# purza.net
KiCad netlist of a schematic drawn in EAGLE
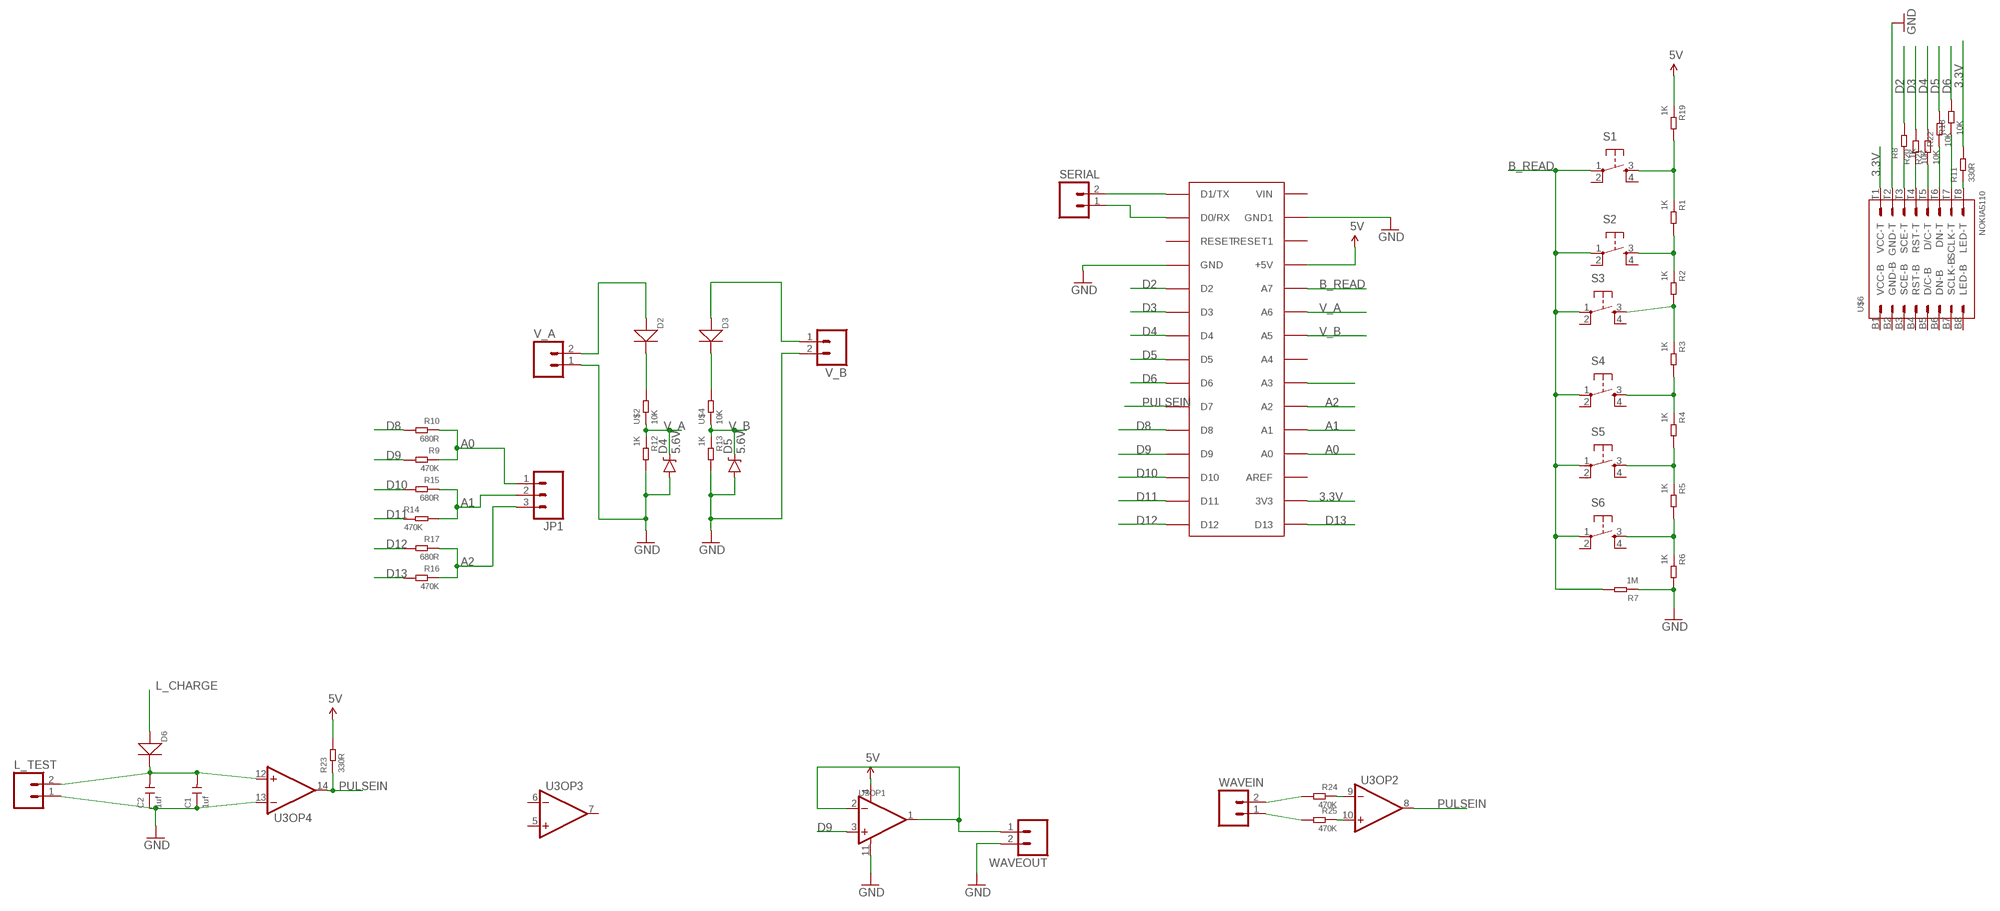
[diagram p0: schematic, sheet 1]

(export (version "E")
  (design (tool "Eeschema 10.0.6"))
  (components
    (comp (ref "C1")
      (value "1uf")
      (footprint "eagle-import:C0805")
      (fields (field (name "MPN") "CC0805KKX7R8BB105"))
      (libsource (lib "eagle-import") (part "CERAMIC-1UF-25V-10%-X7R(0805)"))
    )
    (comp (ref "C2")
      (value "1uf")
      (footprint "eagle-import:C0805")
      (fields (field (name "MPN") "CC0805KKX7R8BB105"))
      (libsource (lib "eagle-import") (part "CERAMIC-1UF-25V-10%-X7R(0805)"))
    )
    (comp (ref "D2")
      (value "DIODE'1206'")
      (footprint "eagle-import:SOD-123")
      (libsource (lib "eagle-import") (part "DIODE'1206'"))
    )
    (comp (ref "D3")
      (value "DIODE'1206'")
      (footprint "eagle-import:SOD-123")
      (libsource (lib "eagle-import") (part "DIODE'1206'"))
    )
    (comp (ref "D4")
      (value "5.6V")
      (footprint "eagle-import:SOD-323")
      (libsource (lib "eagle-import") (part "DIODE-ZENER5.6V"))
    )
    (comp (ref "D5")
      (value "5.6V")
      (footprint "eagle-import:SOD-323")
      (libsource (lib "eagle-import") (part "DIODE-ZENER5.6V"))
    )
    (comp (ref "D6")
      (value "DIODE'1206'")
      (footprint "eagle-import:SOD-123")
      (libsource (lib "eagle-import") (part "DIODE'1206'"))
    )
    (comp (ref "JP1")
      (value "M03LOCK")
      (footprint "eagle-import:1X03_LOCK")
      (libsource (lib "eagle-import") (part "M03LOCK"))
    )
    (comp (ref "L_TEST")
      (value "M02LOCK")
      (footprint "eagle-import:1X02_LOCK")
      (libsource (lib "eagle-import") (part "M02LOCK"))
    )
    (comp (ref "R1")
      (value "1K")
      (footprint "eagle-import:R0603")
      (fields (field (name "MPN") "RC0603FR-071KL"))
      (libsource (lib "eagle-import") (part "SMD-RES-1K-1%-1/10W(0603)"))
    )
    (comp (ref "R2")
      (value "1K")
      (footprint "eagle-import:R0603")
      (fields (field (name "MPN") "RC0603FR-071KL"))
      (libsource (lib "eagle-import") (part "SMD-RES-1K-1%-1/10W(0603)"))
    )
    (comp (ref "R3")
      (value "1K")
      (footprint "eagle-import:R0603")
      (fields (field (name "MPN") "RC0603FR-071KL"))
      (libsource (lib "eagle-import") (part "SMD-RES-1K-1%-1/10W(0603)"))
    )
    (comp (ref "R4")
      (value "1K")
      (footprint "eagle-import:R0603")
      (fields (field (name "MPN") "RC0603FR-071KL"))
      (libsource (lib "eagle-import") (part "SMD-RES-1K-1%-1/10W(0603)"))
    )
    (comp (ref "R5")
      (value "1K")
      (footprint "eagle-import:R0603")
      (fields (field (name "MPN") "RC0603FR-071KL"))
      (libsource (lib "eagle-import") (part "SMD-RES-1K-1%-1/10W(0603)"))
    )
    (comp (ref "R6")
      (value "1K")
      (footprint "eagle-import:R0603")
      (fields (field (name "MPN") "RC0603FR-071KL"))
      (libsource (lib "eagle-import") (part "SMD-RES-1K-1%-1/10W(0603)"))
    )
    (comp (ref "R7")
      (value "1M")
      (footprint "eagle-import:R0603")
      (fields (field (name "MPN") "RC0603FR-071ML"))
      (libsource (lib "eagle-import") (part "SMD-RES-1M-1%-1/10W(0603)"))
    )
    (comp (ref "R8")
      (value "1K")
      (footprint "eagle-import:R0603")
      (fields (field (name "MPN") "RC0603FR-071KL"))
      (libsource (lib "eagle-import") (part "SMD-RES-1K-1%-1/10W(0603)"))
    )
    (comp (ref "R9")
      (value "470K")
      (footprint "eagle-import:R0603")
      (fields (field (name "MPN") "RC0603FR-07470KL"))
      (libsource (lib "eagle-import") (part "SMD-RES-470K-1%-1/10W(0603)"))
    )
    (comp (ref "R10")
      (value "680R")
      (footprint "eagle-import:R0603")
      (fields (field (name "MPN") "RC0603FR-07680RL"))
      (libsource (lib "eagle-import") (part "SMD-RES-680R-1%-1/10W(0603)"))
    )
    (comp (ref "R11")
      (value "330R")
      (footprint "eagle-import:R0603")
      (fields (field (name "MPN") "RC0603FR-07330RL"))
      (libsource (lib "eagle-import") (part "SMD-RES-330R-1%-1/10W(0603)"))
    )
    (comp (ref "R12")
      (value "1K")
      (footprint "eagle-import:R0603")
      (fields (field (name "MPN") "RC0603FR-071KL"))
      (libsource (lib "eagle-import") (part "SMD-RES-1K-1%-1/10W(0603)"))
    )
    (comp (ref "R13")
      (value "1K")
      (footprint "eagle-import:R0603")
      (fields (field (name "MPN") "RC0603FR-071KL"))
      (libsource (lib "eagle-import") (part "SMD-RES-1K-1%-1/10W(0603)"))
    )
    (comp (ref "R14")
      (value "470K")
      (footprint "eagle-import:R0603")
      (fields (field (name "MPN") "RC0603FR-07470KL"))
      (libsource (lib "eagle-import") (part "SMD-RES-470K-1%-1/10W(0603)"))
    )
    (comp (ref "R15")
      (value "680R")
      (footprint "eagle-import:R0603")
      (fields (field (name "MPN") "RC0603FR-07680RL"))
      (libsource (lib "eagle-import") (part "SMD-RES-680R-1%-1/10W(0603)"))
    )
    (comp (ref "R16")
      (value "470K")
      (footprint "eagle-import:R0603")
      (fields (field (name "MPN") "RC0603FR-07470KL"))
      (libsource (lib "eagle-import") (part "SMD-RES-470K-1%-1/10W(0603)"))
    )
    (comp (ref "R17")
      (value "680R")
      (footprint "eagle-import:R0603")
      (fields (field (name "MPN") "RC0603FR-07680RL"))
      (libsource (lib "eagle-import") (part "SMD-RES-680R-1%-1/10W(0603)"))
    )
    (comp (ref "R18")
      (value "10K")
      (footprint "eagle-import:R0603")
      (fields (field (name "MPN") "RC0603FR-0710KL"))
      (libsource (lib "eagle-import") (part "SMD-RES-10K-1%-1/10W(0603)"))
    )
    (comp (ref "R19")
      (value "1K")
      (footprint "eagle-import:R0603")
      (fields (field (name "MPN") "RC0603FR-071KL"))
      (libsource (lib "eagle-import") (part "SMD-RES-1K-1%-1/10W(0603)"))
    )
    (comp (ref "R20")
      (value "10K")
      (footprint "eagle-import:R0603")
      (fields (field (name "MPN") "RC0603FR-0710KL"))
      (libsource (lib "eagle-import") (part "SMD-RES-10K-1%-1/10W(0603)"))
    )
    (comp (ref "R21")
      (value "10K")
      (footprint "eagle-import:R0603")
      (fields (field (name "MPN") "RC0603FR-0710KL"))
      (libsource (lib "eagle-import") (part "SMD-RES-10K-1%-1/10W(0603)"))
    )
    (comp (ref "R22")
      (value "10K")
      (footprint "eagle-import:R0603")
      (fields (field (name "MPN") "RC0603FR-0710KL"))
      (libsource (lib "eagle-import") (part "SMD-RES-10K-1%-1/10W(0603)"))
    )
    (comp (ref "R23")
      (value "330R")
      (footprint "eagle-import:R0603")
      (fields (field (name "MPN") "RC0603FR-07330RL"))
      (libsource (lib "eagle-import") (part "SMD-RES-330R-1%-1/10W(0603)"))
    )
    (comp (ref "R24")
      (value "470K")
      (footprint "eagle-import:R0603")
      (fields (field (name "MPN") "RC0603FR-07470KL"))
      (libsource (lib "eagle-import") (part "SMD-RES-470K-1%-1/10W(0603)"))
    )
    (comp (ref "R25")
      (value "470K")
      (footprint "eagle-import:R0603")
      (fields (field (name "MPN") "RC0603FR-07470KL"))
      (libsource (lib "eagle-import") (part "SMD-RES-470K-1%-1/10W(0603)"))
    )
    (comp (ref "S1")
      (value "TAC_SWITCHPTH")
      (footprint "eagle-import:TACTILE-PTH")
      (libsource (lib "eagle-import") (part "TAC_SWITCHPTH"))
    )
    (comp (ref "S2")
      (value "TAC_SWITCHPTH")
      (footprint "eagle-import:TACTILE-PTH")
      (libsource (lib "eagle-import") (part "TAC_SWITCHPTH"))
    )
    (comp (ref "S3")
      (value "TAC_SWITCHPTH")
      (footprint "eagle-import:TACTILE-PTH")
      (libsource (lib "eagle-import") (part "TAC_SWITCHPTH"))
    )
    (comp (ref "S4")
      (value "TAC_SWITCHPTH")
      (footprint "eagle-import:TACTILE-PTH")
      (libsource (lib "eagle-import") (part "TAC_SWITCHPTH"))
    )
    (comp (ref "S5")
      (value "TAC_SWITCHPTH")
      (footprint "eagle-import:TACTILE-PTH")
      (libsource (lib "eagle-import") (part "TAC_SWITCHPTH"))
    )
    (comp (ref "S6")
      (value "TAC_SWITCHPTH")
      (footprint "eagle-import:TACTILE-PTH")
      (libsource (lib "eagle-import") (part "TAC_SWITCHPTH"))
    )
    (comp (ref "SERIAL")
      (value "M02LOCK")
      (footprint "eagle-import:1X02_LOCK")
      (libsource (lib "eagle-import") (part "M02LOCK"))
    )
    (comp (ref "U$1")
      (value "ARDUINONANO")
      (footprint "eagle-import:PDIP-32")
      (libsource (lib "eagle-import") (part "ARDUINONANO"))
    )
    (comp (ref "U$2")
      (value "10K")
      (footprint "eagle-import:R0805")
      (fields (field (name "MPN") "RC0805FR-0710KL"))
      (libsource (lib "eagle-import") (part "SMD-RES-10K-1%-1/8W(0805)"))
    )
    (comp (ref "U$4")
      (value "10K")
      (footprint "eagle-import:R0805")
      (fields (field (name "MPN") "RC0805FR-0710KL"))
      (libsource (lib "eagle-import") (part "SMD-RES-10K-1%-1/8W(0805)"))
    )
    (comp (ref "U$6")
      (value "NOKIA5110")
      (footprint "eagle-import:NOKIA5110")
      (libsource (lib "eagle-import") (part "NOKIA5110"))
    )
    (comp (ref "U3")
      (value "AMPLIFIER-LMV324IDR(SOIC14)")
      (footprint "eagle-import:SOIC14-1.27-9.3X4.3MM")
      (fields (field (name "MPN") "LMV324IDR"))
      (libsource (lib "eagle-import") (part "AMPLIFIER-LMV324IDR(SOIC14)"))
    )
    (comp (ref "V_A")
      (value "M02LOCK")
      (footprint "eagle-import:1X02_LOCK")
      (libsource (lib "eagle-import") (part "M02LOCK"))
    )
    (comp (ref "V_B")
      (value "M02LOCK")
      (footprint "eagle-import:1X02_LOCK")
      (libsource (lib "eagle-import") (part "M02LOCK"))
    )
    (comp (ref "WAVEIN")
      (value "M02LOCK")
      (footprint "eagle-import:1X02_LOCK")
      (libsource (lib "eagle-import") (part "M02LOCK"))
    )
    (comp (ref "WAVEOUT")
      (value "M02LOCK")
      (footprint "eagle-import:1X02_LOCK")
      (libsource (lib "eagle-import") (part "M02LOCK"))
    )
  )
  (nets
    (net (code "1") (name "/3.3V") (class "Default")
      (node (ref "R11") (pin "2") (pinfunction "2_2") (pintype "passive"))
      (node (ref "U$1") (pin "3V3") (pinfunction "3V3_3V3") (pintype "bidirectional"))
      (node (ref "U$6") (pin "T1") (pinfunction "VCC-T_T1") (pintype "bidirectional"))
    )
    (net (code "2") (name "/A0") (class "Default")
      (node (ref "JP1") (pin "1") (pinfunction "1_1") (pintype "passive"))
      (node (ref "R10") (pin "1") (pinfunction "1_1") (pintype "passive"))
      (node (ref "R9") (pin "1") (pinfunction "1_1") (pintype "passive"))
      (node (ref "U$1") (pin "A0") (pinfunction "A0_A0") (pintype "bidirectional"))
    )
    (net (code "3") (name "/A1") (class "Default")
      (node (ref "JP1") (pin "2") (pinfunction "2_2") (pintype "passive"))
      (node (ref "R14") (pin "2") (pinfunction "2_2") (pintype "passive"))
      (node (ref "R15") (pin "1") (pinfunction "1_1") (pintype "passive"))
      (node (ref "U$1") (pin "A1") (pinfunction "A1_A1") (pintype "bidirectional"))
    )
    (net (code "4") (name "/A2") (class "Default")
      (node (ref "JP1") (pin "3") (pinfunction "3_3") (pintype "passive"))
      (node (ref "R16") (pin "1") (pinfunction "1_1") (pintype "passive"))
      (node (ref "R17") (pin "1") (pinfunction "1_1") (pintype "passive"))
      (node (ref "U$1") (pin "A2") (pinfunction "A2_A2") (pintype "bidirectional"))
    )
    (net (code "5") (name "/B_READ") (class "Default")
      (node (ref "R7") (pin "2") (pinfunction "2_2") (pintype "passive"))
      (node (ref "S1") (pin "1") (pinfunction "1_1") (pintype "passive"))
      (node (ref "S2") (pin "1") (pinfunction "1_1") (pintype "passive"))
      (node (ref "S3") (pin "1") (pinfunction "1_1") (pintype "passive"))
      (node (ref "S4") (pin "1") (pinfunction "1_1") (pintype "passive"))
      (node (ref "S5") (pin "1") (pinfunction "1_1") (pintype "passive"))
      (node (ref "S6") (pin "1") (pinfunction "1_1") (pintype "passive"))
      (node (ref "U$1") (pin "A7") (pinfunction "A7_A7") (pintype "bidirectional"))
    )
    (net (code "6") (name "/D2") (class "Default")
      (node (ref "R8") (pin "2") (pinfunction "2_2") (pintype "passive"))
      (node (ref "U$1") (pin "D2") (pinfunction "D2_D2") (pintype "bidirectional"))
    )
    (net (code "7") (name "/D3") (class "Default")
      (node (ref "R20") (pin "2") (pinfunction "2_2") (pintype "passive"))
      (node (ref "U$1") (pin "D3") (pinfunction "D3_D3") (pintype "bidirectional"))
    )
    (net (code "8") (name "/D4") (class "Default")
      (node (ref "R21") (pin "2") (pinfunction "2_2") (pintype "passive"))
      (node (ref "U$1") (pin "D4") (pinfunction "D4_D4") (pintype "bidirectional"))
    )
    (net (code "9") (name "/D5") (class "Default")
      (node (ref "R22") (pin "2") (pinfunction "2_2") (pintype "passive"))
      (node (ref "U$1") (pin "D5") (pinfunction "D5_D5") (pintype "bidirectional"))
    )
    (net (code "10") (name "/D6") (class "Default")
      (node (ref "R18") (pin "2") (pinfunction "2_2") (pintype "passive"))
      (node (ref "U$1") (pin "D6") (pinfunction "D6_D6") (pintype "bidirectional"))
    )
    (net (code "11") (name "/D8") (class "Default")
      (node (ref "R10") (pin "2") (pinfunction "2_2") (pintype "passive"))
      (node (ref "U$1") (pin "D8") (pinfunction "D8_D8") (pintype "bidirectional"))
    )
    (net (code "12") (name "/D9") (class "Default")
      (node (ref "R9") (pin "2") (pinfunction "2_2") (pintype "passive"))
      (node (ref "U$1") (pin "D9") (pinfunction "D9_D9") (pintype "bidirectional"))
      (node (ref "U3") (pin "3") (pinfunction "IN+_3") (pintype "input"))
    )
    (net (code "13") (name "/D10") (class "Default")
      (node (ref "R15") (pin "2") (pinfunction "2_2") (pintype "passive"))
      (node (ref "U$1") (pin "D10") (pinfunction "D10_D10") (pintype "bidirectional"))
    )
    (net (code "14") (name "/D11") (class "Default")
      (node (ref "R14") (pin "1") (pinfunction "1_1") (pintype "passive"))
      (node (ref "U$1") (pin "D11") (pinfunction "D11_D11") (pintype "bidirectional"))
    )
    (net (code "15") (name "/D12") (class "Default")
      (node (ref "R17") (pin "2") (pinfunction "2_2") (pintype "passive"))
      (node (ref "U$1") (pin "D12") (pinfunction "D12_D12") (pintype "bidirectional"))
    )
    (net (code "16") (name "/D13") (class "Default")
      (node (ref "R16") (pin "2") (pinfunction "2_2") (pintype "passive"))
      (node (ref "U$1") (pin "D13") (pinfunction "D13_D13") (pintype "bidirectional"))
    )
    (net (code "17") (name "/L_CHARGE") (class "Default")
      (node (ref "D6") (pin "+") (pinfunction "+_+") (pintype "passive"))
      (node (ref "U$1") (pin "A3") (pinfunction "A3_A3") (pintype "bidirectional"))
    )
    (net (code "18") (name "/PULSEIN") (class "Default")
      (node (ref "R23") (pin "1") (pinfunction "1_1") (pintype "passive"))
      (node (ref "U$1") (pin "D7") (pinfunction "D7_D7") (pintype "bidirectional"))
      (node (ref "U3") (pin "14") (pinfunction "OUT_14") (pintype "output"))
      (node (ref "U3") (pin "8") (pinfunction "OUT_8") (pintype "output"))
    )
    (net (code "19") (name "/V_A") (class "Default")
      (node (ref "D4") (pin "C") (pinfunction "C_C") (pintype "passive"))
      (node (ref "R12") (pin "1") (pinfunction "1_1") (pintype "passive"))
      (node (ref "U$1") (pin "A6") (pinfunction "A6_A6") (pintype "bidirectional"))
      (node (ref "U$2") (pin "1") (pinfunction "1_1") (pintype "passive"))
    )
    (net (code "20") (name "/V_B") (class "Default")
      (node (ref "D5") (pin "C") (pinfunction "C_C") (pintype "passive"))
      (node (ref "R13") (pin "1") (pinfunction "1_1") (pintype "passive"))
      (node (ref "U$1") (pin "A5") (pinfunction "A5_A5") (pintype "bidirectional"))
      (node (ref "U$4") (pin "1") (pinfunction "1_1") (pintype "passive"))
    )
    (net (code "21") (name "5V") (class "Default")
      (node (ref "R19") (pin "1") (pinfunction "1_1") (pintype "passive"))
      (node (ref "R23") (pin "2") (pinfunction "2_2") (pintype "passive"))
      (node (ref "U$1") (pin "+5V") (pinfunction "+5V_+5V") (pintype "bidirectional"))
      (node (ref "U3") (pin "4") (pinfunction "V+_4") (pintype "power_in"))
    )
    (net (code "22") (name "GND") (class "Default")
      (node (ref "C1") (pin "1") (pinfunction "1_1") (pintype "passive"))
      (node (ref "C2") (pin "1") (pinfunction "1_1") (pintype "passive"))
      (node (ref "D4") (pin "A") (pinfunction "A_A") (pintype "passive"))
      (node (ref "D5") (pin "A") (pinfunction "A_A") (pintype "passive"))
      (node (ref "L_TEST") (pin "1") (pinfunction "1_1") (pintype "passive"))
      (node (ref "R12") (pin "2") (pinfunction "2_2") (pintype "passive"))
      (node (ref "R13") (pin "2") (pinfunction "2_2") (pintype "passive"))
      (node (ref "R6") (pin "2") (pinfunction "2_2") (pintype "passive"))
      (node (ref "R7") (pin "1") (pinfunction "1_1") (pintype "passive"))
      (node (ref "U$1") (pin "GND") (pinfunction "GND_GND") (pintype "bidirectional"))
      (node (ref "U$1") (pin "GND1") (pinfunction "GND1_GND1") (pintype "bidirectional"))
      (node (ref "U$6") (pin "T2") (pinfunction "GND-T_T2") (pintype "bidirectional"))
      (node (ref "U3") (pin "11") (pinfunction "V-_11") (pintype "power_in"))
      (node (ref "U3") (pin "13") (pinfunction "IN-_13") (pintype "input"))
      (node (ref "V_A") (pin "1") (pinfunction "1_1") (pintype "passive"))
      (node (ref "V_B") (pin "2") (pinfunction "2_2") (pintype "passive"))
      (node (ref "WAVEOUT") (pin "2") (pinfunction "2_2") (pintype "passive"))
    )
    (net (code "23") (name "Net-(D2-Pad+)") (class "Default")
      (node (ref "D2") (pin "+") (pinfunction "+_+") (pintype "passive"))
      (node (ref "V_A") (pin "2") (pinfunction "2_2") (pintype "passive"))
    )
    (net (code "24") (name "Net-(D2-Pad-)") (class "Default")
      (node (ref "D2") (pin "-") (pinfunction "-_-") (pintype "passive"))
      (node (ref "U$2") (pin "2") (pinfunction "2_2") (pintype "passive"))
    )
    (net (code "25") (name "Net-(D3-Pad+)") (class "Default")
      (node (ref "D3") (pin "+") (pinfunction "+_+") (pintype "passive"))
      (node (ref "V_B") (pin "1") (pinfunction "1_1") (pintype "passive"))
    )
    (net (code "26") (name "Net-(D3-Pad-)") (class "Default")
      (node (ref "D3") (pin "-") (pinfunction "-_-") (pintype "passive"))
      (node (ref "U$4") (pin "2") (pinfunction "2_2") (pintype "passive"))
    )
    (net (code "27") (name "Net-(R1-Pad1)") (class "Default")
      (node (ref "R1") (pin "1") (pinfunction "1_1") (pintype "passive"))
      (node (ref "R19") (pin "2") (pinfunction "2_2") (pintype "passive"))
      (node (ref "S1") (pin "3") (pinfunction "3_3") (pintype "passive"))
    )
    (net (code "28") (name "Net-(R1-Pad2)") (class "Default")
      (node (ref "R1") (pin "2") (pinfunction "2_2") (pintype "passive"))
      (node (ref "R2") (pin "1") (pinfunction "1_1") (pintype "passive"))
      (node (ref "S2") (pin "3") (pinfunction "3_3") (pintype "passive"))
    )
    (net (code "29") (name "Net-(R2-Pad2)") (class "Default")
      (node (ref "R2") (pin "2") (pinfunction "2_2") (pintype "passive"))
      (node (ref "R3") (pin "1") (pinfunction "1_1") (pintype "passive"))
      (node (ref "S3") (pin "3") (pinfunction "3_3") (pintype "passive"))
    )
    (net (code "30") (name "Net-(R3-Pad2)") (class "Default")
      (node (ref "R3") (pin "2") (pinfunction "2_2") (pintype "passive"))
      (node (ref "R4") (pin "1") (pinfunction "1_1") (pintype "passive"))
      (node (ref "S4") (pin "3") (pinfunction "3_3") (pintype "passive"))
    )
    (net (code "31") (name "Net-(R4-Pad2)") (class "Default")
      (node (ref "R4") (pin "2") (pinfunction "2_2") (pintype "passive"))
      (node (ref "R5") (pin "1") (pinfunction "1_1") (pintype "passive"))
      (node (ref "S5") (pin "3") (pinfunction "3_3") (pintype "passive"))
    )
    (net (code "32") (name "Net-(R5-Pad2)") (class "Default")
      (node (ref "R5") (pin "2") (pinfunction "2_2") (pintype "passive"))
      (node (ref "R6") (pin "1") (pinfunction "1_1") (pintype "passive"))
      (node (ref "S6") (pin "3") (pinfunction "3_3") (pintype "passive"))
    )
    (net (code "33") (name "Net-(R24-Pad2)") (class "Default")
      (node (ref "R24") (pin "2") (pinfunction "2_2") (pintype "passive"))
      (node (ref "WAVEIN") (pin "2") (pinfunction "2_2") (pintype "passive"))
    )
    (net (code "34") (name "Net-(R25-Pad2)") (class "Default")
      (node (ref "R25") (pin "2") (pinfunction "2_2") (pintype "passive"))
      (node (ref "WAVEIN") (pin "1") (pinfunction "1_1") (pintype "passive"))
    )
    (net (code "35") (name "Net-(SERIAL-Pad1)") (class "Default")
      (node (ref "SERIAL") (pin "1") (pinfunction "1_1") (pintype "passive"))
      (node (ref "U$1") (pin "D0/RX") (pinfunction "D0/RX_D0/RX") (pintype "bidirectional"))
    )
    (net (code "36") (name "Net-(SERIAL-Pad2)") (class "Default")
      (node (ref "SERIAL") (pin "2") (pinfunction "2_2") (pintype "passive"))
      (node (ref "U$1") (pin "D1/TX") (pinfunction "D1/TX_D1/TX") (pintype "bidirectional"))
    )
    (net (code "37") (name "Net-(U$6-DN-T)") (class "Default")
      (node (ref "R22") (pin "1") (pinfunction "1_1") (pintype "passive"))
      (node (ref "U$6") (pin "T6") (pinfunction "DN-T_T6") (pintype "bidirectional"))
    )
    (net (code "38") (name "Net-(U$6-D{slash}C-T)") (class "Default")
      (node (ref "R21") (pin "1") (pinfunction "1_1") (pintype "passive"))
      (node (ref "U$6") (pin "T5") (pinfunction "D/C-T_T5") (pintype "bidirectional"))
    )
    (net (code "39") (name "Net-(U$6-LED-T)") (class "Default")
      (node (ref "R11") (pin "1") (pinfunction "1_1") (pintype "passive"))
      (node (ref "U$6") (pin "T8") (pinfunction "LED-T_T8") (pintype "bidirectional"))
    )
    (net (code "40") (name "Net-(U$6-RST-T)") (class "Default")
      (node (ref "R20") (pin "1") (pinfunction "1_1") (pintype "passive"))
      (node (ref "U$6") (pin "T4") (pinfunction "RST-T_T4") (pintype "bidirectional"))
    )
    (net (code "41") (name "Net-(U$6-SCE-T)") (class "Default")
      (node (ref "R8") (pin "1") (pinfunction "1_1") (pintype "passive"))
      (node (ref "U$6") (pin "T3") (pinfunction "SCE-T_T3") (pintype "bidirectional"))
    )
    (net (code "42") (name "Net-(U$6-SCLK-T)") (class "Default")
      (node (ref "R18") (pin "1") (pinfunction "1_1") (pintype "passive"))
      (node (ref "U$6") (pin "T7") (pinfunction "SCLK-T_T7") (pintype "bidirectional"))
    )
    (net (code "43") (name "Net-(U3A-IN-)") (class "Default")
      (node (ref "U3") (pin "1") (pinfunction "OUT_1") (pintype "output"))
      (node (ref "U3") (pin "2") (pinfunction "IN-_2") (pintype "input"))
      (node (ref "WAVEOUT") (pin "1") (pinfunction "1_1") (pintype "passive"))
    )
    (net (code "44") (name "Net-(U3B-IN+)") (class "Default")
      (node (ref "R25") (pin "1") (pinfunction "1_1") (pintype "passive"))
      (node (ref "U3") (pin "10") (pinfunction "IN+_10") (pintype "input"))
    )
    (net (code "45") (name "Net-(U3B-IN-)") (class "Default")
      (node (ref "R24") (pin "1") (pinfunction "1_1") (pintype "passive"))
      (node (ref "U3") (pin "9") (pinfunction "IN-_9") (pintype "input"))
    )
    (net (code "46") (name "Net-(U3D-IN+)") (class "Default")
      (node (ref "C1") (pin "2") (pinfunction "2_2") (pintype "passive"))
      (node (ref "C2") (pin "2") (pinfunction "2_2") (pintype "passive"))
      (node (ref "D6") (pin "-") (pinfunction "-_-") (pintype "passive"))
      (node (ref "L_TEST") (pin "2") (pinfunction "2_2") (pintype "passive"))
      (node (ref "U3") (pin "12") (pinfunction "IN+_12") (pintype "input"))
    )
    (net (code "47") (name "unconnected-(S1-Pad2)") (class "Default")
      (node (ref "S1") (pin "2") (pinfunction "2_2") (pintype "passive"))
    )
    (net (code "48") (name "unconnected-(S1-Pad4)") (class "Default")
      (node (ref "S1") (pin "4") (pinfunction "4_4") (pintype "passive"))
    )
    (net (code "49") (name "unconnected-(S2-Pad2)") (class "Default")
      (node (ref "S2") (pin "2") (pinfunction "2_2") (pintype "passive"))
    )
    (net (code "50") (name "unconnected-(S2-Pad4)") (class "Default")
      (node (ref "S2") (pin "4") (pinfunction "4_4") (pintype "passive"))
    )
    (net (code "51") (name "unconnected-(S3-Pad2)") (class "Default")
      (node (ref "S3") (pin "2") (pinfunction "2_2") (pintype "passive"))
    )
    (net (code "52") (name "unconnected-(S3-Pad4)") (class "Default")
      (node (ref "S3") (pin "4") (pinfunction "4_4") (pintype "passive"))
    )
    (net (code "53") (name "unconnected-(S4-Pad2)") (class "Default")
      (node (ref "S4") (pin "2") (pinfunction "2_2") (pintype "passive"))
    )
    (net (code "54") (name "unconnected-(S4-Pad4)") (class "Default")
      (node (ref "S4") (pin "4") (pinfunction "4_4") (pintype "passive"))
    )
    (net (code "55") (name "unconnected-(S5-Pad2)") (class "Default")
      (node (ref "S5") (pin "2") (pinfunction "2_2") (pintype "passive"))
    )
    (net (code "56") (name "unconnected-(S5-Pad4)") (class "Default")
      (node (ref "S5") (pin "4") (pinfunction "4_4") (pintype "passive"))
    )
    (net (code "57") (name "unconnected-(S6-Pad2)") (class "Default")
      (node (ref "S6") (pin "2") (pinfunction "2_2") (pintype "passive"))
    )
    (net (code "58") (name "unconnected-(S6-Pad4)") (class "Default")
      (node (ref "S6") (pin "4") (pinfunction "4_4") (pintype "passive"))
    )
    (net (code "59") (name "unconnected-(U$1-PadA4)") (class "Default")
      (node (ref "U$1") (pin "A4") (pinfunction "A4_A4") (pintype "bidirectional"))
    )
    (net (code "60") (name "unconnected-(U$1-PadAREF)") (class "Default")
      (node (ref "U$1") (pin "AREF") (pinfunction "AREF_AREF") (pintype "bidirectional"))
    )
    (net (code "61") (name "unconnected-(U$1-PadRESET)") (class "Default")
      (node (ref "U$1") (pin "RESET") (pinfunction "RESET_RESET") (pintype "bidirectional"))
    )
    (net (code "62") (name "unconnected-(U$1-PadRESET1)") (class "Default")
      (node (ref "U$1") (pin "RESET1") (pinfunction "RESET1_RESET1") (pintype "bidirectional"))
    )
    (net (code "63") (name "unconnected-(U$1-PadVIN)") (class "Default")
      (node (ref "U$1") (pin "VIN") (pinfunction "VIN_VIN") (pintype "bidirectional"))
    )
    (net (code "64") (name "unconnected-(U$6-DN-B-PadB6)") (class "Default")
      (node (ref "U$6") (pin "B6") (pinfunction "DN-B_B6") (pintype "bidirectional"))
    )
    (net (code "65") (name "unconnected-(U$6-D{slash}C-B-PadB5)") (class "Default")
      (node (ref "U$6") (pin "B5") (pinfunction "D/C-B_B5") (pintype "bidirectional"))
    )
    (net (code "66") (name "unconnected-(U$6-GND-B-PadB2)") (class "Default")
      (node (ref "U$6") (pin "B2") (pinfunction "GND-B_B2") (pintype "bidirectional"))
    )
    (net (code "67") (name "unconnected-(U$6-LED-B-PadB8)") (class "Default")
      (node (ref "U$6") (pin "B8") (pinfunction "LED-B_B8") (pintype "bidirectional"))
    )
    (net (code "68") (name "unconnected-(U$6-RST-B-PadB4)") (class "Default")
      (node (ref "U$6") (pin "B4") (pinfunction "RST-B_B4") (pintype "bidirectional"))
    )
    (net (code "69") (name "unconnected-(U$6-SCE-B-PadB3)") (class "Default")
      (node (ref "U$6") (pin "B3") (pinfunction "SCE-B_B3") (pintype "bidirectional"))
    )
    (net (code "70") (name "unconnected-(U$6-SCLK-B-PadB7)") (class "Default")
      (node (ref "U$6") (pin "B7") (pinfunction "SCLK-B_B7") (pintype "bidirectional"))
    )
    (net (code "71") (name "unconnected-(U$6-VCC-B-PadB1)") (class "Default")
      (node (ref "U$6") (pin "B1") (pinfunction "VCC-B_B1") (pintype "bidirectional"))
    )
    (net (code "72") (name "unconnected-(U3C-IN+-Pad5)") (class "Default")
      (node (ref "U3") (pin "5") (pinfunction "IN+_5") (pintype "input"))
    )
    (net (code "73") (name "unconnected-(U3C-IN--Pad6)") (class "Default")
      (node (ref "U3") (pin "6") (pinfunction "IN-_6") (pintype "input"))
    )
    (net (code "74") (name "unconnected-(U3C-OUT-Pad7)") (class "Default")
      (node (ref "U3") (pin "7") (pinfunction "OUT_7") (pintype "output"))
    )
  )
)
